# Temperature_Sensor.net
KiCad netlist of a schematic drawn in Altium Designer
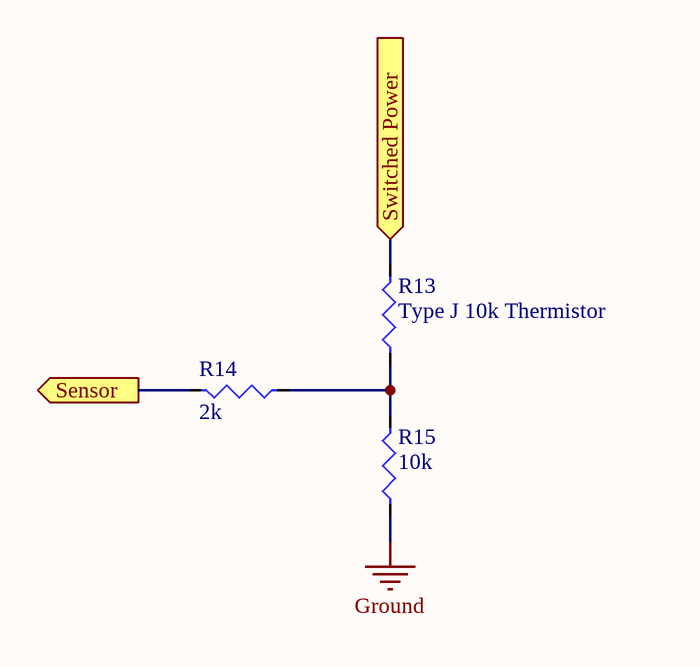
[diagram p0: Temperature Sensor.SchDoc]

(export (version "E")
  (design (tool "Eeschema 10.0.6"))
  (components
    (comp (ref "R13")
      (value "Resistor")
      (footprint "RESISTOR THT 3W 0.05HOLE 900MIL")
      (fields (field (name "TOLERANCE") "1%") (field (name "QUICKVALUE") "Type J 10k Thermistor"))
      (libsource (lib "EDC Standard Library") (part "Resistor"))
    )
    (comp (ref "R14")
      (value "Resistor")
      (footprint "RESISTOR THT 3W 0.05HOLE 900MIL")
      (fields (field (name "TOLERANCE") "1%") (field (name "QUICKVALUE") "2k"))
      (libsource (lib "EDC Standard Library") (part "Resistor"))
    )
    (comp (ref "R15")
      (value "Resistor")
      (footprint "RESISTOR THT 3W 0.05HOLE 900MIL")
      (fields (field (name "TOLERANCE") "1%") (field (name "QUICKVALUE") "10k"))
      (libsource (lib "EDC Standard Library") (part "Resistor"))
    )
  )
  (nets
    (net (code "1") (name "/Sensor") (class "Default")
      (node (ref "R14") (pin "2") (pinfunction "2_2") (pintype "passive"))
    )
    (net (code "2") (name "/Switched Power") (class "Default")
      (node (ref "R13") (pin "2") (pinfunction "2_2") (pintype "passive"))
    )
    (net (code "3") (name "Ground") (class "Default")
      (node (ref "R15") (pin "1") (pinfunction "1_1") (pintype "passive"))
    )
    (net (code "4") (name "Net-(R13-Pad1)") (class "Default")
      (node (ref "R13") (pin "1") (pinfunction "1_1") (pintype "passive"))
      (node (ref "R14") (pin "1") (pinfunction "1_1") (pintype "passive"))
      (node (ref "R15") (pin "2") (pinfunction "2_2") (pintype "passive"))
    )
  )
)
